# Nusbio_-_Ex_Bread_Board.net
KiCad netlist of a schematic drawn in EAGLE
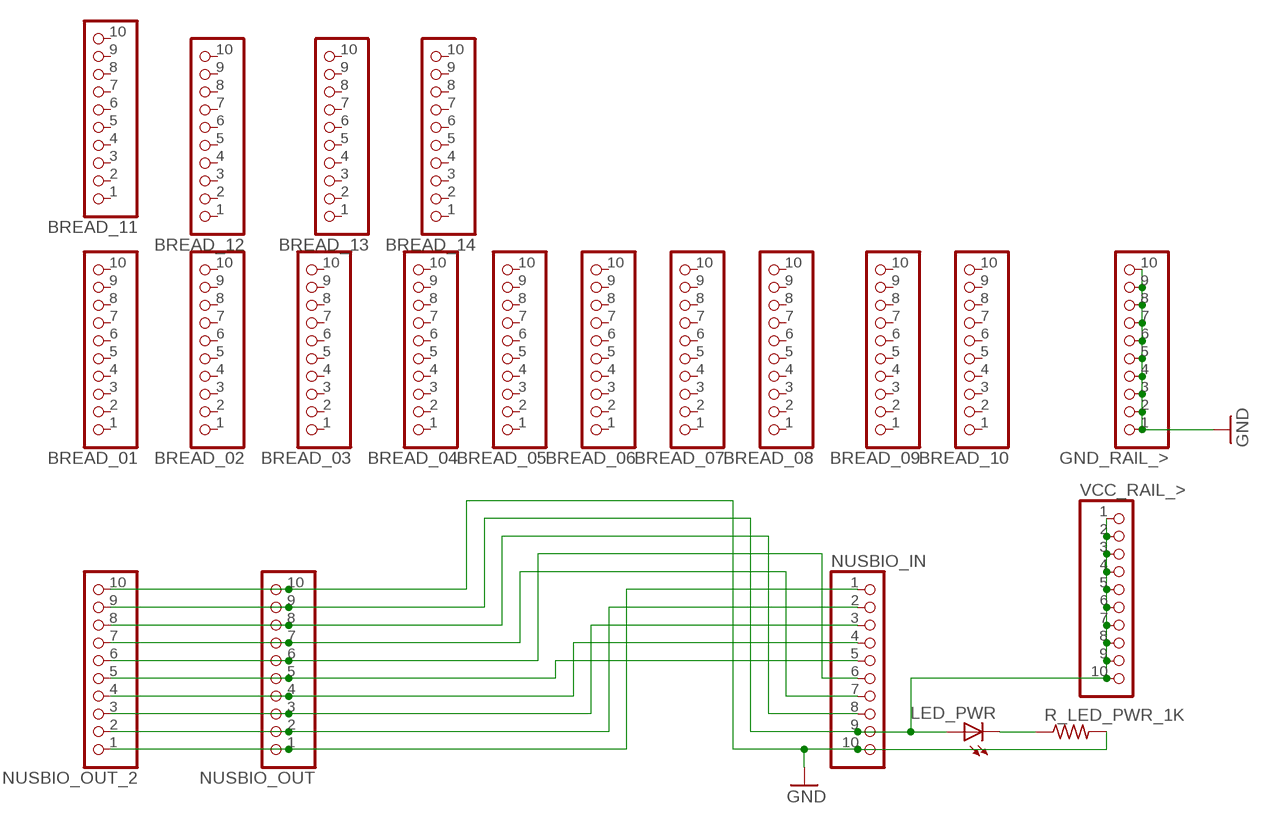
[diagram p0: schematic, sheet 1]

(export (version "E")
  (design (tool "Eeschema 10.0.6"))
  (components
    (comp (ref "BREAD_01")
      (value "PINHD-1X10")
      (footprint "eagle-import:1X10-BIG")
      (libsource (lib "eagle-import") (part "PINHD-1X10"))
    )
    (comp (ref "BREAD_02")
      (value "PINHD-1X10")
      (footprint "eagle-import:1X10-BIG")
      (libsource (lib "eagle-import") (part "PINHD-1X10"))
    )
    (comp (ref "BREAD_03")
      (value "PINHD-1X10")
      (footprint "eagle-import:1X10-BIG")
      (libsource (lib "eagle-import") (part "PINHD-1X10"))
    )
    (comp (ref "BREAD_04")
      (value "PINHD-1X10")
      (footprint "eagle-import:1X10-BIG")
      (libsource (lib "eagle-import") (part "PINHD-1X10"))
    )
    (comp (ref "BREAD_05")
      (value "PINHD-1X10")
      (footprint "eagle-import:1X10-BIG")
      (libsource (lib "eagle-import") (part "PINHD-1X10"))
    )
    (comp (ref "BREAD_06")
      (value "PINHD-1X10")
      (footprint "eagle-import:1X10-BIG")
      (libsource (lib "eagle-import") (part "PINHD-1X10"))
    )
    (comp (ref "BREAD_07")
      (value "PINHD-1X10")
      (footprint "eagle-import:1X10-BIG")
      (libsource (lib "eagle-import") (part "PINHD-1X10"))
    )
    (comp (ref "BREAD_08")
      (value "PINHD-1X10")
      (footprint "eagle-import:1X10-BIG")
      (libsource (lib "eagle-import") (part "PINHD-1X10"))
    )
    (comp (ref "BREAD_09")
      (value "PINHD-1X10")
      (footprint "eagle-import:1X10-BIG")
      (libsource (lib "eagle-import") (part "PINHD-1X10"))
    )
    (comp (ref "BREAD_10")
      (value "PINHD-1X10")
      (footprint "eagle-import:1X10-BIG")
      (libsource (lib "eagle-import") (part "PINHD-1X10"))
    )
    (comp (ref "BREAD_11")
      (value "PINHD-1X10")
      (footprint "eagle-import:1X10-BIG")
      (libsource (lib "eagle-import") (part "PINHD-1X10"))
    )
    (comp (ref "BREAD_12")
      (value "PINHD-1X10")
      (footprint "eagle-import:1X10-BIG")
      (libsource (lib "eagle-import") (part "PINHD-1X10"))
    )
    (comp (ref "BREAD_13")
      (value "PINHD-1X10")
      (footprint "eagle-import:1X10-BIG")
      (libsource (lib "eagle-import") (part "PINHD-1X10"))
    )
    (comp (ref "BREAD_14")
      (value "PINHD-1X10")
      (footprint "eagle-import:1X10-BIG")
      (libsource (lib "eagle-import") (part "PINHD-1X10"))
    )
    (comp (ref "GND_RAIL_>")
      (value "PINHD-1X10")
      (footprint "eagle-import:1X10-BIG")
      (libsource (lib "eagle-import") (part "PINHD-1X10"))
    )
    (comp (ref "LED_PWR")
      (value "LEDSMT1206")
      (footprint "eagle-import:1206")
      (libsource (lib "eagle-import") (part "LEDSMT1206"))
    )
    (comp (ref "NUSBIO_IN")
      (value "PINHD-1X10")
      (footprint "eagle-import:1X10-BIG")
      (libsource (lib "eagle-import") (part "PINHD-1X10"))
    )
    (comp (ref "NUSBIO_OUT")
      (value "PINHD-1X10")
      (footprint "eagle-import:1X10-BIG")
      (libsource (lib "eagle-import") (part "PINHD-1X10"))
    )
    (comp (ref "NUSBIO_OUT_2")
      (value "PINHD-1X10")
      (footprint "eagle-import:1X10-BIG")
      (libsource (lib "eagle-import") (part "PINHD-1X10"))
    )
    (comp (ref "R_LED_PWR_1K")
      (value "R-US_R1206")
      (footprint "eagle-import:R1206")
      (libsource (lib "eagle-import") (part "R-US_R1206"))
    )
    (comp (ref "VCC_RAIL_>")
      (value "PINHD-1X10")
      (footprint "eagle-import:1X10-BIG")
      (libsource (lib "eagle-import") (part "PINHD-1X10"))
    )
  )
  (nets
    (net (code "1") (name "GND") (class "Default")
      (node (ref "GND_RAIL_>") (pin "1") (pinfunction "1_1") (pintype "passive"))
      (node (ref "GND_RAIL_>") (pin "10") (pinfunction "10_10") (pintype "passive"))
      (node (ref "GND_RAIL_>") (pin "2") (pinfunction "2_2") (pintype "passive"))
      (node (ref "GND_RAIL_>") (pin "3") (pinfunction "3_3") (pintype "passive"))
      (node (ref "GND_RAIL_>") (pin "4") (pinfunction "4_4") (pintype "passive"))
      (node (ref "GND_RAIL_>") (pin "5") (pinfunction "5_5") (pintype "passive"))
      (node (ref "GND_RAIL_>") (pin "6") (pinfunction "6_6") (pintype "passive"))
      (node (ref "GND_RAIL_>") (pin "7") (pinfunction "7_7") (pintype "passive"))
      (node (ref "GND_RAIL_>") (pin "8") (pinfunction "8_8") (pintype "passive"))
      (node (ref "GND_RAIL_>") (pin "9") (pinfunction "9_9") (pintype "passive"))
      (node (ref "NUSBIO_IN") (pin "10") (pinfunction "10_10") (pintype "passive"))
      (node (ref "NUSBIO_OUT") (pin "10") (pinfunction "10_10") (pintype "passive"))
      (node (ref "NUSBIO_OUT_2") (pin "10") (pinfunction "10_10") (pintype "passive"))
      (node (ref "R_LED_PWR_1K") (pin "2") (pinfunction "2_2") (pintype "passive"))
    )
    (net (code "2") (name "Net-(LED_PWR-PadA)") (class "Default")
      (node (ref "LED_PWR") (pin "A") (pinfunction "A_A") (pintype "passive"))
      (node (ref "NUSBIO_IN") (pin "9") (pinfunction "9_9") (pintype "passive"))
      (node (ref "NUSBIO_OUT") (pin "9") (pinfunction "9_9") (pintype "passive"))
      (node (ref "NUSBIO_OUT_2") (pin "9") (pinfunction "9_9") (pintype "passive"))
      (node (ref "VCC_RAIL_>") (pin "1") (pinfunction "1_1") (pintype "passive"))
      (node (ref "VCC_RAIL_>") (pin "10") (pinfunction "10_10") (pintype "passive"))
      (node (ref "VCC_RAIL_>") (pin "2") (pinfunction "2_2") (pintype "passive"))
      (node (ref "VCC_RAIL_>") (pin "3") (pinfunction "3_3") (pintype "passive"))
      (node (ref "VCC_RAIL_>") (pin "4") (pinfunction "4_4") (pintype "passive"))
      (node (ref "VCC_RAIL_>") (pin "5") (pinfunction "5_5") (pintype "passive"))
      (node (ref "VCC_RAIL_>") (pin "6") (pinfunction "6_6") (pintype "passive"))
      (node (ref "VCC_RAIL_>") (pin "7") (pinfunction "7_7") (pintype "passive"))
      (node (ref "VCC_RAIL_>") (pin "8") (pinfunction "8_8") (pintype "passive"))
      (node (ref "VCC_RAIL_>") (pin "9") (pinfunction "9_9") (pintype "passive"))
    )
    (net (code "3") (name "Net-(LED_PWR-PadC)") (class "Default")
      (node (ref "LED_PWR") (pin "C") (pinfunction "C_C") (pintype "passive"))
      (node (ref "R_LED_PWR_1K") (pin "1") (pinfunction "1_1") (pintype "passive"))
    )
    (net (code "4") (name "Net-(NUSBIO_IN-Pad1)") (class "Default")
      (node (ref "NUSBIO_IN") (pin "1") (pinfunction "1_1") (pintype "passive"))
      (node (ref "NUSBIO_OUT") (pin "1") (pinfunction "1_1") (pintype "passive"))
      (node (ref "NUSBIO_OUT_2") (pin "1") (pinfunction "1_1") (pintype "passive"))
    )
    (net (code "5") (name "Net-(NUSBIO_IN-Pad2)") (class "Default")
      (node (ref "NUSBIO_IN") (pin "2") (pinfunction "2_2") (pintype "passive"))
      (node (ref "NUSBIO_OUT") (pin "2") (pinfunction "2_2") (pintype "passive"))
      (node (ref "NUSBIO_OUT_2") (pin "2") (pinfunction "2_2") (pintype "passive"))
    )
    (net (code "6") (name "Net-(NUSBIO_IN-Pad3)") (class "Default")
      (node (ref "NUSBIO_IN") (pin "3") (pinfunction "3_3") (pintype "passive"))
      (node (ref "NUSBIO_OUT") (pin "3") (pinfunction "3_3") (pintype "passive"))
      (node (ref "NUSBIO_OUT_2") (pin "3") (pinfunction "3_3") (pintype "passive"))
    )
    (net (code "7") (name "Net-(NUSBIO_IN-Pad4)") (class "Default")
      (node (ref "NUSBIO_IN") (pin "4") (pinfunction "4_4") (pintype "passive"))
      (node (ref "NUSBIO_OUT") (pin "4") (pinfunction "4_4") (pintype "passive"))
      (node (ref "NUSBIO_OUT_2") (pin "4") (pinfunction "4_4") (pintype "passive"))
    )
    (net (code "8") (name "Net-(NUSBIO_IN-Pad5)") (class "Default")
      (node (ref "NUSBIO_IN") (pin "5") (pinfunction "5_5") (pintype "passive"))
      (node (ref "NUSBIO_OUT") (pin "5") (pinfunction "5_5") (pintype "passive"))
      (node (ref "NUSBIO_OUT_2") (pin "5") (pinfunction "5_5") (pintype "passive"))
    )
    (net (code "9") (name "Net-(NUSBIO_IN-Pad6)") (class "Default")
      (node (ref "NUSBIO_IN") (pin "6") (pinfunction "6_6") (pintype "passive"))
      (node (ref "NUSBIO_OUT") (pin "6") (pinfunction "6_6") (pintype "passive"))
      (node (ref "NUSBIO_OUT_2") (pin "6") (pinfunction "6_6") (pintype "passive"))
    )
    (net (code "10") (name "Net-(NUSBIO_IN-Pad7)") (class "Default")
      (node (ref "NUSBIO_IN") (pin "7") (pinfunction "7_7") (pintype "passive"))
      (node (ref "NUSBIO_OUT") (pin "7") (pinfunction "7_7") (pintype "passive"))
      (node (ref "NUSBIO_OUT_2") (pin "7") (pinfunction "7_7") (pintype "passive"))
    )
    (net (code "11") (name "Net-(NUSBIO_IN-Pad8)") (class "Default")
      (node (ref "NUSBIO_IN") (pin "8") (pinfunction "8_8") (pintype "passive"))
      (node (ref "NUSBIO_OUT") (pin "8") (pinfunction "8_8") (pintype "passive"))
      (node (ref "NUSBIO_OUT_2") (pin "8") (pinfunction "8_8") (pintype "passive"))
    )
    (net (code "12") (name "unconnected-(BREAD_01-Pad1)") (class "Default")
      (node (ref "BREAD_01") (pin "1") (pinfunction "1_1") (pintype "passive"))
    )
    (net (code "13") (name "unconnected-(BREAD_01-Pad2)") (class "Default")
      (node (ref "BREAD_01") (pin "2") (pinfunction "2_2") (pintype "passive"))
    )
    (net (code "14") (name "unconnected-(BREAD_01-Pad3)") (class "Default")
      (node (ref "BREAD_01") (pin "3") (pinfunction "3_3") (pintype "passive"))
    )
    (net (code "15") (name "unconnected-(BREAD_01-Pad4)") (class "Default")
      (node (ref "BREAD_01") (pin "4") (pinfunction "4_4") (pintype "passive"))
    )
    (net (code "16") (name "unconnected-(BREAD_01-Pad5)") (class "Default")
      (node (ref "BREAD_01") (pin "5") (pinfunction "5_5") (pintype "passive"))
    )
    (net (code "17") (name "unconnected-(BREAD_01-Pad6)") (class "Default")
      (node (ref "BREAD_01") (pin "6") (pinfunction "6_6") (pintype "passive"))
    )
    (net (code "18") (name "unconnected-(BREAD_01-Pad7)") (class "Default")
      (node (ref "BREAD_01") (pin "7") (pinfunction "7_7") (pintype "passive"))
    )
    (net (code "19") (name "unconnected-(BREAD_01-Pad8)") (class "Default")
      (node (ref "BREAD_01") (pin "8") (pinfunction "8_8") (pintype "passive"))
    )
    (net (code "20") (name "unconnected-(BREAD_01-Pad9)") (class "Default")
      (node (ref "BREAD_01") (pin "9") (pinfunction "9_9") (pintype "passive"))
    )
    (net (code "21") (name "unconnected-(BREAD_01-Pad10)") (class "Default")
      (node (ref "BREAD_01") (pin "10") (pinfunction "10_10") (pintype "passive"))
    )
    (net (code "22") (name "unconnected-(BREAD_02-Pad1)") (class "Default")
      (node (ref "BREAD_02") (pin "1") (pinfunction "1_1") (pintype "passive"))
    )
    (net (code "23") (name "unconnected-(BREAD_02-Pad2)") (class "Default")
      (node (ref "BREAD_02") (pin "2") (pinfunction "2_2") (pintype "passive"))
    )
    (net (code "24") (name "unconnected-(BREAD_02-Pad3)") (class "Default")
      (node (ref "BREAD_02") (pin "3") (pinfunction "3_3") (pintype "passive"))
    )
    (net (code "25") (name "unconnected-(BREAD_02-Pad4)") (class "Default")
      (node (ref "BREAD_02") (pin "4") (pinfunction "4_4") (pintype "passive"))
    )
    (net (code "26") (name "unconnected-(BREAD_02-Pad5)") (class "Default")
      (node (ref "BREAD_02") (pin "5") (pinfunction "5_5") (pintype "passive"))
    )
    (net (code "27") (name "unconnected-(BREAD_02-Pad6)") (class "Default")
      (node (ref "BREAD_02") (pin "6") (pinfunction "6_6") (pintype "passive"))
    )
    (net (code "28") (name "unconnected-(BREAD_02-Pad7)") (class "Default")
      (node (ref "BREAD_02") (pin "7") (pinfunction "7_7") (pintype "passive"))
    )
    (net (code "29") (name "unconnected-(BREAD_02-Pad8)") (class "Default")
      (node (ref "BREAD_02") (pin "8") (pinfunction "8_8") (pintype "passive"))
    )
    (net (code "30") (name "unconnected-(BREAD_02-Pad9)") (class "Default")
      (node (ref "BREAD_02") (pin "9") (pinfunction "9_9") (pintype "passive"))
    )
    (net (code "31") (name "unconnected-(BREAD_02-Pad10)") (class "Default")
      (node (ref "BREAD_02") (pin "10") (pinfunction "10_10") (pintype "passive"))
    )
    (net (code "32") (name "unconnected-(BREAD_03-Pad1)") (class "Default")
      (node (ref "BREAD_03") (pin "1") (pinfunction "1_1") (pintype "passive"))
    )
    (net (code "33") (name "unconnected-(BREAD_03-Pad2)") (class "Default")
      (node (ref "BREAD_03") (pin "2") (pinfunction "2_2") (pintype "passive"))
    )
    (net (code "34") (name "unconnected-(BREAD_03-Pad3)") (class "Default")
      (node (ref "BREAD_03") (pin "3") (pinfunction "3_3") (pintype "passive"))
    )
    (net (code "35") (name "unconnected-(BREAD_03-Pad4)") (class "Default")
      (node (ref "BREAD_03") (pin "4") (pinfunction "4_4") (pintype "passive"))
    )
    (net (code "36") (name "unconnected-(BREAD_03-Pad5)") (class "Default")
      (node (ref "BREAD_03") (pin "5") (pinfunction "5_5") (pintype "passive"))
    )
    (net (code "37") (name "unconnected-(BREAD_03-Pad6)") (class "Default")
      (node (ref "BREAD_03") (pin "6") (pinfunction "6_6") (pintype "passive"))
    )
    (net (code "38") (name "unconnected-(BREAD_03-Pad7)") (class "Default")
      (node (ref "BREAD_03") (pin "7") (pinfunction "7_7") (pintype "passive"))
    )
    (net (code "39") (name "unconnected-(BREAD_03-Pad8)") (class "Default")
      (node (ref "BREAD_03") (pin "8") (pinfunction "8_8") (pintype "passive"))
    )
    (net (code "40") (name "unconnected-(BREAD_03-Pad9)") (class "Default")
      (node (ref "BREAD_03") (pin "9") (pinfunction "9_9") (pintype "passive"))
    )
    (net (code "41") (name "unconnected-(BREAD_03-Pad10)") (class "Default")
      (node (ref "BREAD_03") (pin "10") (pinfunction "10_10") (pintype "passive"))
    )
    (net (code "42") (name "unconnected-(BREAD_04-Pad1)") (class "Default")
      (node (ref "BREAD_04") (pin "1") (pinfunction "1_1") (pintype "passive"))
    )
    (net (code "43") (name "unconnected-(BREAD_04-Pad2)") (class "Default")
      (node (ref "BREAD_04") (pin "2") (pinfunction "2_2") (pintype "passive"))
    )
    (net (code "44") (name "unconnected-(BREAD_04-Pad3)") (class "Default")
      (node (ref "BREAD_04") (pin "3") (pinfunction "3_3") (pintype "passive"))
    )
    (net (code "45") (name "unconnected-(BREAD_04-Pad4)") (class "Default")
      (node (ref "BREAD_04") (pin "4") (pinfunction "4_4") (pintype "passive"))
    )
    (net (code "46") (name "unconnected-(BREAD_04-Pad5)") (class "Default")
      (node (ref "BREAD_04") (pin "5") (pinfunction "5_5") (pintype "passive"))
    )
    (net (code "47") (name "unconnected-(BREAD_04-Pad6)") (class "Default")
      (node (ref "BREAD_04") (pin "6") (pinfunction "6_6") (pintype "passive"))
    )
    (net (code "48") (name "unconnected-(BREAD_04-Pad7)") (class "Default")
      (node (ref "BREAD_04") (pin "7") (pinfunction "7_7") (pintype "passive"))
    )
    (net (code "49") (name "unconnected-(BREAD_04-Pad8)") (class "Default")
      (node (ref "BREAD_04") (pin "8") (pinfunction "8_8") (pintype "passive"))
    )
    (net (code "50") (name "unconnected-(BREAD_04-Pad9)") (class "Default")
      (node (ref "BREAD_04") (pin "9") (pinfunction "9_9") (pintype "passive"))
    )
    (net (code "51") (name "unconnected-(BREAD_04-Pad10)") (class "Default")
      (node (ref "BREAD_04") (pin "10") (pinfunction "10_10") (pintype "passive"))
    )
    (net (code "52") (name "unconnected-(BREAD_05-Pad1)") (class "Default")
      (node (ref "BREAD_05") (pin "1") (pinfunction "1_1") (pintype "passive"))
    )
    (net (code "53") (name "unconnected-(BREAD_05-Pad2)") (class "Default")
      (node (ref "BREAD_05") (pin "2") (pinfunction "2_2") (pintype "passive"))
    )
    (net (code "54") (name "unconnected-(BREAD_05-Pad3)") (class "Default")
      (node (ref "BREAD_05") (pin "3") (pinfunction "3_3") (pintype "passive"))
    )
    (net (code "55") (name "unconnected-(BREAD_05-Pad4)") (class "Default")
      (node (ref "BREAD_05") (pin "4") (pinfunction "4_4") (pintype "passive"))
    )
    (net (code "56") (name "unconnected-(BREAD_05-Pad5)") (class "Default")
      (node (ref "BREAD_05") (pin "5") (pinfunction "5_5") (pintype "passive"))
    )
    (net (code "57") (name "unconnected-(BREAD_05-Pad6)") (class "Default")
      (node (ref "BREAD_05") (pin "6") (pinfunction "6_6") (pintype "passive"))
    )
    (net (code "58") (name "unconnected-(BREAD_05-Pad7)") (class "Default")
      (node (ref "BREAD_05") (pin "7") (pinfunction "7_7") (pintype "passive"))
    )
    (net (code "59") (name "unconnected-(BREAD_05-Pad8)") (class "Default")
      (node (ref "BREAD_05") (pin "8") (pinfunction "8_8") (pintype "passive"))
    )
    (net (code "60") (name "unconnected-(BREAD_05-Pad9)") (class "Default")
      (node (ref "BREAD_05") (pin "9") (pinfunction "9_9") (pintype "passive"))
    )
    (net (code "61") (name "unconnected-(BREAD_05-Pad10)") (class "Default")
      (node (ref "BREAD_05") (pin "10") (pinfunction "10_10") (pintype "passive"))
    )
    (net (code "62") (name "unconnected-(BREAD_06-Pad1)") (class "Default")
      (node (ref "BREAD_06") (pin "1") (pinfunction "1_1") (pintype "passive"))
    )
    (net (code "63") (name "unconnected-(BREAD_06-Pad2)") (class "Default")
      (node (ref "BREAD_06") (pin "2") (pinfunction "2_2") (pintype "passive"))
    )
    (net (code "64") (name "unconnected-(BREAD_06-Pad3)") (class "Default")
      (node (ref "BREAD_06") (pin "3") (pinfunction "3_3") (pintype "passive"))
    )
    (net (code "65") (name "unconnected-(BREAD_06-Pad4)") (class "Default")
      (node (ref "BREAD_06") (pin "4") (pinfunction "4_4") (pintype "passive"))
    )
    (net (code "66") (name "unconnected-(BREAD_06-Pad5)") (class "Default")
      (node (ref "BREAD_06") (pin "5") (pinfunction "5_5") (pintype "passive"))
    )
    (net (code "67") (name "unconnected-(BREAD_06-Pad6)") (class "Default")
      (node (ref "BREAD_06") (pin "6") (pinfunction "6_6") (pintype "passive"))
    )
    (net (code "68") (name "unconnected-(BREAD_06-Pad7)") (class "Default")
      (node (ref "BREAD_06") (pin "7") (pinfunction "7_7") (pintype "passive"))
    )
    (net (code "69") (name "unconnected-(BREAD_06-Pad8)") (class "Default")
      (node (ref "BREAD_06") (pin "8") (pinfunction "8_8") (pintype "passive"))
    )
    (net (code "70") (name "unconnected-(BREAD_06-Pad9)") (class "Default")
      (node (ref "BREAD_06") (pin "9") (pinfunction "9_9") (pintype "passive"))
    )
    (net (code "71") (name "unconnected-(BREAD_06-Pad10)") (class "Default")
      (node (ref "BREAD_06") (pin "10") (pinfunction "10_10") (pintype "passive"))
    )
    (net (code "72") (name "unconnected-(BREAD_07-Pad1)") (class "Default")
      (node (ref "BREAD_07") (pin "1") (pinfunction "1_1") (pintype "passive"))
    )
    (net (code "73") (name "unconnected-(BREAD_07-Pad2)") (class "Default")
      (node (ref "BREAD_07") (pin "2") (pinfunction "2_2") (pintype "passive"))
    )
    (net (code "74") (name "unconnected-(BREAD_07-Pad3)") (class "Default")
      (node (ref "BREAD_07") (pin "3") (pinfunction "3_3") (pintype "passive"))
    )
    (net (code "75") (name "unconnected-(BREAD_07-Pad4)") (class "Default")
      (node (ref "BREAD_07") (pin "4") (pinfunction "4_4") (pintype "passive"))
    )
    (net (code "76") (name "unconnected-(BREAD_07-Pad5)") (class "Default")
      (node (ref "BREAD_07") (pin "5") (pinfunction "5_5") (pintype "passive"))
    )
    (net (code "77") (name "unconnected-(BREAD_07-Pad6)") (class "Default")
      (node (ref "BREAD_07") (pin "6") (pinfunction "6_6") (pintype "passive"))
    )
    (net (code "78") (name "unconnected-(BREAD_07-Pad7)") (class "Default")
      (node (ref "BREAD_07") (pin "7") (pinfunction "7_7") (pintype "passive"))
    )
    (net (code "79") (name "unconnected-(BREAD_07-Pad8)") (class "Default")
      (node (ref "BREAD_07") (pin "8") (pinfunction "8_8") (pintype "passive"))
    )
    (net (code "80") (name "unconnected-(BREAD_07-Pad9)") (class "Default")
      (node (ref "BREAD_07") (pin "9") (pinfunction "9_9") (pintype "passive"))
    )
    (net (code "81") (name "unconnected-(BREAD_07-Pad10)") (class "Default")
      (node (ref "BREAD_07") (pin "10") (pinfunction "10_10") (pintype "passive"))
    )
    (net (code "82") (name "unconnected-(BREAD_08-Pad1)") (class "Default")
      (node (ref "BREAD_08") (pin "1") (pinfunction "1_1") (pintype "passive"))
    )
    (net (code "83") (name "unconnected-(BREAD_08-Pad2)") (class "Default")
      (node (ref "BREAD_08") (pin "2") (pinfunction "2_2") (pintype "passive"))
    )
    (net (code "84") (name "unconnected-(BREAD_08-Pad3)") (class "Default")
      (node (ref "BREAD_08") (pin "3") (pinfunction "3_3") (pintype "passive"))
    )
    (net (code "85") (name "unconnected-(BREAD_08-Pad4)") (class "Default")
      (node (ref "BREAD_08") (pin "4") (pinfunction "4_4") (pintype "passive"))
    )
    (net (code "86") (name "unconnected-(BREAD_08-Pad5)") (class "Default")
      (node (ref "BREAD_08") (pin "5") (pinfunction "5_5") (pintype "passive"))
    )
    (net (code "87") (name "unconnected-(BREAD_08-Pad6)") (class "Default")
      (node (ref "BREAD_08") (pin "6") (pinfunction "6_6") (pintype "passive"))
    )
    (net (code "88") (name "unconnected-(BREAD_08-Pad7)") (class "Default")
      (node (ref "BREAD_08") (pin "7") (pinfunction "7_7") (pintype "passive"))
    )
    (net (code "89") (name "unconnected-(BREAD_08-Pad8)") (class "Default")
      (node (ref "BREAD_08") (pin "8") (pinfunction "8_8") (pintype "passive"))
    )
    (net (code "90") (name "unconnected-(BREAD_08-Pad9)") (class "Default")
      (node (ref "BREAD_08") (pin "9") (pinfunction "9_9") (pintype "passive"))
    )
    (net (code "91") (name "unconnected-(BREAD_08-Pad10)") (class "Default")
      (node (ref "BREAD_08") (pin "10") (pinfunction "10_10") (pintype "passive"))
    )
    (net (code "92") (name "unconnected-(BREAD_09-Pad1)") (class "Default")
      (node (ref "BREAD_09") (pin "1") (pinfunction "1_1") (pintype "passive"))
    )
    (net (code "93") (name "unconnected-(BREAD_09-Pad2)") (class "Default")
      (node (ref "BREAD_09") (pin "2") (pinfunction "2_2") (pintype "passive"))
    )
    (net (code "94") (name "unconnected-(BREAD_09-Pad3)") (class "Default")
      (node (ref "BREAD_09") (pin "3") (pinfunction "3_3") (pintype "passive"))
    )
    (net (code "95") (name "unconnected-(BREAD_09-Pad4)") (class "Default")
      (node (ref "BREAD_09") (pin "4") (pinfunction "4_4") (pintype "passive"))
    )
    (net (code "96") (name "unconnected-(BREAD_09-Pad5)") (class "Default")
      (node (ref "BREAD_09") (pin "5") (pinfunction "5_5") (pintype "passive"))
    )
    (net (code "97") (name "unconnected-(BREAD_09-Pad6)") (class "Default")
      (node (ref "BREAD_09") (pin "6") (pinfunction "6_6") (pintype "passive"))
    )
    (net (code "98") (name "unconnected-(BREAD_09-Pad7)") (class "Default")
      (node (ref "BREAD_09") (pin "7") (pinfunction "7_7") (pintype "passive"))
    )
    (net (code "99") (name "unconnected-(BREAD_09-Pad8)") (class "Default")
      (node (ref "BREAD_09") (pin "8") (pinfunction "8_8") (pintype "passive"))
    )
    (net (code "100") (name "unconnected-(BREAD_09-Pad9)") (class "Default")
      (node (ref "BREAD_09") (pin "9") (pinfunction "9_9") (pintype "passive"))
    )
    (net (code "101") (name "unconnected-(BREAD_09-Pad10)") (class "Default")
      (node (ref "BREAD_09") (pin "10") (pinfunction "10_10") (pintype "passive"))
    )
    (net (code "102") (name "unconnected-(BREAD_10-Pad1)") (class "Default")
      (node (ref "BREAD_10") (pin "1") (pinfunction "1_1") (pintype "passive"))
    )
    (net (code "103") (name "unconnected-(BREAD_10-Pad2)") (class "Default")
      (node (ref "BREAD_10") (pin "2") (pinfunction "2_2") (pintype "passive"))
    )
    (net (code "104") (name "unconnected-(BREAD_10-Pad3)") (class "Default")
      (node (ref "BREAD_10") (pin "3") (pinfunction "3_3") (pintype "passive"))
    )
    (net (code "105") (name "unconnected-(BREAD_10-Pad4)") (class "Default")
      (node (ref "BREAD_10") (pin "4") (pinfunction "4_4") (pintype "passive"))
    )
    (net (code "106") (name "unconnected-(BREAD_10-Pad5)") (class "Default")
      (node (ref "BREAD_10") (pin "5") (pinfunction "5_5") (pintype "passive"))
    )
    (net (code "107") (name "unconnected-(BREAD_10-Pad6)") (class "Default")
      (node (ref "BREAD_10") (pin "6") (pinfunction "6_6") (pintype "passive"))
    )
    (net (code "108") (name "unconnected-(BREAD_10-Pad7)") (class "Default")
      (node (ref "BREAD_10") (pin "7") (pinfunction "7_7") (pintype "passive"))
    )
    (net (code "109") (name "unconnected-(BREAD_10-Pad8)") (class "Default")
      (node (ref "BREAD_10") (pin "8") (pinfunction "8_8") (pintype "passive"))
    )
    (net (code "110") (name "unconnected-(BREAD_10-Pad9)") (class "Default")
      (node (ref "BREAD_10") (pin "9") (pinfunction "9_9") (pintype "passive"))
    )
    (net (code "111") (name "unconnected-(BREAD_10-Pad10)") (class "Default")
      (node (ref "BREAD_10") (pin "10") (pinfunction "10_10") (pintype "passive"))
    )
    (net (code "112") (name "unconnected-(BREAD_11-Pad1)") (class "Default")
      (node (ref "BREAD_11") (pin "1") (pinfunction "1_1") (pintype "passive"))
    )
    (net (code "113") (name "unconnected-(BREAD_11-Pad2)") (class "Default")
      (node (ref "BREAD_11") (pin "2") (pinfunction "2_2") (pintype "passive"))
    )
    (net (code "114") (name "unconnected-(BREAD_11-Pad3)") (class "Default")
      (node (ref "BREAD_11") (pin "3") (pinfunction "3_3") (pintype "passive"))
    )
    (net (code "115") (name "unconnected-(BREAD_11-Pad4)") (class "Default")
      (node (ref "BREAD_11") (pin "4") (pinfunction "4_4") (pintype "passive"))
    )
    (net (code "116") (name "unconnected-(BREAD_11-Pad5)") (class "Default")
      (node (ref "BREAD_11") (pin "5") (pinfunction "5_5") (pintype "passive"))
    )
    (net (code "117") (name "unconnected-(BREAD_11-Pad6)") (class "Default")
      (node (ref "BREAD_11") (pin "6") (pinfunction "6_6") (pintype "passive"))
    )
    (net (code "118") (name "unconnected-(BREAD_11-Pad7)") (class "Default")
      (node (ref "BREAD_11") (pin "7") (pinfunction "7_7") (pintype "passive"))
    )
    (net (code "119") (name "unconnected-(BREAD_11-Pad8)") (class "Default")
      (node (ref "BREAD_11") (pin "8") (pinfunction "8_8") (pintype "passive"))
    )
    (net (code "120") (name "unconnected-(BREAD_11-Pad9)") (class "Default")
      (node (ref "BREAD_11") (pin "9") (pinfunction "9_9") (pintype "passive"))
    )
    (net (code "121") (name "unconnected-(BREAD_11-Pad10)") (class "Default")
      (node (ref "BREAD_11") (pin "10") (pinfunction "10_10") (pintype "passive"))
    )
    (net (code "122") (name "unconnected-(BREAD_12-Pad1)") (class "Default")
      (node (ref "BREAD_12") (pin "1") (pinfunction "1_1") (pintype "passive"))
    )
    (net (code "123") (name "unconnected-(BREAD_12-Pad2)") (class "Default")
      (node (ref "BREAD_12") (pin "2") (pinfunction "2_2") (pintype "passive"))
    )
    (net (code "124") (name "unconnected-(BREAD_12-Pad3)") (class "Default")
      (node (ref "BREAD_12") (pin "3") (pinfunction "3_3") (pintype "passive"))
    )
    (net (code "125") (name "unconnected-(BREAD_12-Pad4)") (class "Default")
      (node (ref "BREAD_12") (pin "4") (pinfunction "4_4") (pintype "passive"))
    )
    (net (code "126") (name "unconnected-(BREAD_12-Pad5)") (class "Default")
      (node (ref "BREAD_12") (pin "5") (pinfunction "5_5") (pintype "passive"))
    )
    (net (code "127") (name "unconnected-(BREAD_12-Pad6)") (class "Default")
      (node (ref "BREAD_12") (pin "6") (pinfunction "6_6") (pintype "passive"))
    )
    (net (code "128") (name "unconnected-(BREAD_12-Pad7)") (class "Default")
      (node (ref "BREAD_12") (pin "7") (pinfunction "7_7") (pintype "passive"))
    )
    (net (code "129") (name "unconnected-(BREAD_12-Pad8)") (class "Default")
      (node (ref "BREAD_12") (pin "8") (pinfunction "8_8") (pintype "passive"))
    )
    (net (code "130") (name "unconnected-(BREAD_12-Pad9)") (class "Default")
      (node (ref "BREAD_12") (pin "9") (pinfunction "9_9") (pintype "passive"))
    )
    (net (code "131") (name "unconnected-(BREAD_12-Pad10)") (class "Default")
      (node (ref "BREAD_12") (pin "10") (pinfunction "10_10") (pintype "passive"))
    )
    (net (code "132") (name "unconnected-(BREAD_13-Pad1)") (class "Default")
      (node (ref "BREAD_13") (pin "1") (pinfunction "1_1") (pintype "passive"))
    )
    (net (code "133") (name "unconnected-(BREAD_13-Pad2)") (class "Default")
      (node (ref "BREAD_13") (pin "2") (pinfunction "2_2") (pintype "passive"))
    )
    (net (code "134") (name "unconnected-(BREAD_13-Pad3)") (class "Default")
      (node (ref "BREAD_13") (pin "3") (pinfunction "3_3") (pintype "passive"))
    )
    (net (code "135") (name "unconnected-(BREAD_13-Pad4)") (class "Default")
      (node (ref "BREAD_13") (pin "4") (pinfunction "4_4") (pintype "passive"))
    )
    (net (code "136") (name "unconnected-(BREAD_13-Pad5)") (class "Default")
      (node (ref "BREAD_13") (pin "5") (pinfunction "5_5") (pintype "passive"))
    )
    (net (code "137") (name "unconnected-(BREAD_13-Pad6)") (class "Default")
      (node (ref "BREAD_13") (pin "6") (pinfunction "6_6") (pintype "passive"))
    )
    (net (code "138") (name "unconnected-(BREAD_13-Pad7)") (class "Default")
      (node (ref "BREAD_13") (pin "7") (pinfunction "7_7") (pintype "passive"))
    )
    (net (code "139") (name "unconnected-(BREAD_13-Pad8)") (class "Default")
      (node (ref "BREAD_13") (pin "8") (pinfunction "8_8") (pintype "passive"))
    )
    (net (code "140") (name "unconnected-(BREAD_13-Pad9)") (class "Default")
      (node (ref "BREAD_13") (pin "9") (pinfunction "9_9") (pintype "passive"))
    )
    (net (code "141") (name "unconnected-(BREAD_13-Pad10)") (class "Default")
      (node (ref "BREAD_13") (pin "10") (pinfunction "10_10") (pintype "passive"))
    )
    (net (code "142") (name "unconnected-(BREAD_14-Pad1)") (class "Default")
      (node (ref "BREAD_14") (pin "1") (pinfunction "1_1") (pintype "passive"))
    )
    (net (code "143") (name "unconnected-(BREAD_14-Pad2)") (class "Default")
      (node (ref "BREAD_14") (pin "2") (pinfunction "2_2") (pintype "passive"))
    )
    (net (code "144") (name "unconnected-(BREAD_14-Pad3)") (class "Default")
      (node (ref "BREAD_14") (pin "3") (pinfunction "3_3") (pintype "passive"))
    )
    (net (code "145") (name "unconnected-(BREAD_14-Pad4)") (class "Default")
      (node (ref "BREAD_14") (pin "4") (pinfunction "4_4") (pintype "passive"))
    )
    (net (code "146") (name "unconnected-(BREAD_14-Pad5)") (class "Default")
      (node (ref "BREAD_14") (pin "5") (pinfunction "5_5") (pintype "passive"))
    )
    (net (code "147") (name "unconnected-(BREAD_14-Pad6)") (class "Default")
      (node (ref "BREAD_14") (pin "6") (pinfunction "6_6") (pintype "passive"))
    )
    (net (code "148") (name "unconnected-(BREAD_14-Pad7)") (class "Default")
      (node (ref "BREAD_14") (pin "7") (pinfunction "7_7") (pintype "passive"))
    )
    (net (code "149") (name "unconnected-(BREAD_14-Pad8)") (class "Default")
      (node (ref "BREAD_14") (pin "8") (pinfunction "8_8") (pintype "passive"))
    )
    (net (code "150") (name "unconnected-(BREAD_14-Pad9)") (class "Default")
      (node (ref "BREAD_14") (pin "9") (pinfunction "9_9") (pintype "passive"))
    )
    (net (code "151") (name "unconnected-(BREAD_14-Pad10)") (class "Default")
      (node (ref "BREAD_14") (pin "10") (pinfunction "10_10") (pintype "passive"))
    )
  )
)
